# esp8266_01.net
KiCad netlist of a schematic drawn in EAGLE
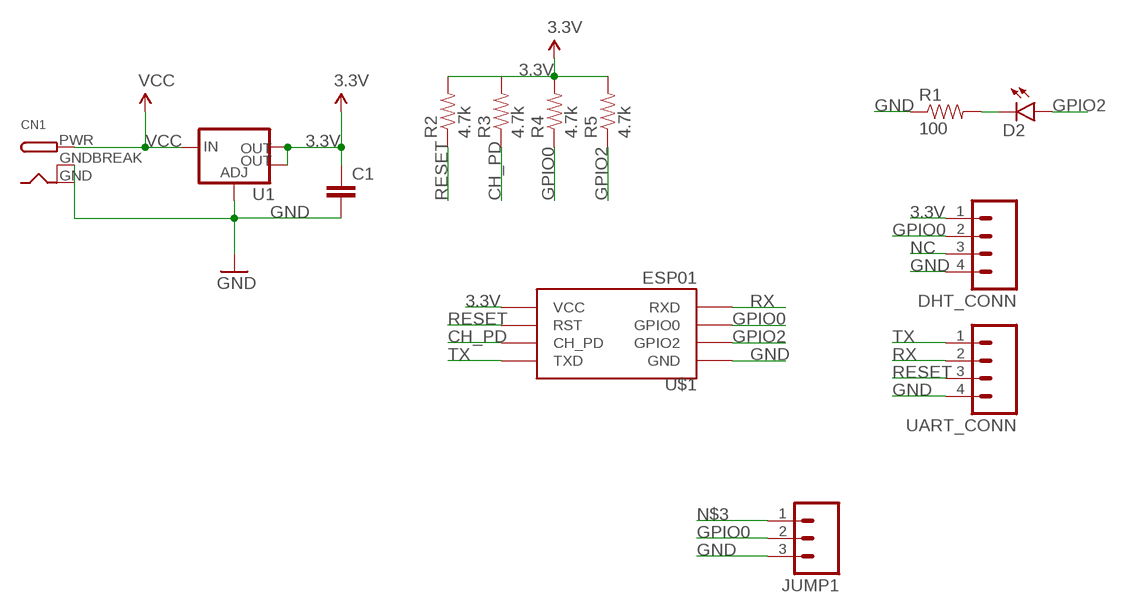
[diagram p0: schematic, sheet 1]

(export (version "E")
  (design (tool "Eeschema 10.0.6"))
  (components
    (comp (ref "C1")
      (value "CAP0805")
      (footprint "eagle-import:0805")
      (libsource (lib "eagle-import") (part "CAP0805"))
    )
    (comp (ref "CN1")
      (value "DCBARRELPTH")
      (footprint "eagle-import:DCJACK_2MM_PTH")
      (libsource (lib "eagle-import") (part "DCBARRELPTH"))
    )
    (comp (ref "D2")
      (value "LED5MM")
      (footprint "eagle-import:LED5MM")
      (libsource (lib "eagle-import") (part "LED5MM"))
    )
    (comp (ref "DHT_CONN")
      (value "M04LONGPADS")
      (footprint "eagle-import:1X04_LONGPADS")
      (libsource (lib "eagle-import") (part "M04LONGPADS"))
    )
    (comp (ref "JUMP1")
      (value "M03LOCK_LONGPADS")
      (footprint "eagle-import:1X03_LOCK_LONGPADS")
      (libsource (lib "eagle-import") (part "M03LOCK_LONGPADS"))
    )
    (comp (ref "R1")
      (value "100")
      (footprint "eagle-import:0805")
      (libsource (lib "eagle-import") (part "RESISTOR0805-RES"))
    )
    (comp (ref "R2")
      (value "4.7k")
      (footprint "eagle-import:0805")
      (libsource (lib "eagle-import") (part "RESISTOR0805-RES"))
    )
    (comp (ref "R3")
      (value "4.7k")
      (footprint "eagle-import:0805")
      (libsource (lib "eagle-import") (part "RESISTOR0805-RES"))
    )
    (comp (ref "R4")
      (value "4.7k")
      (footprint "eagle-import:0805")
      (libsource (lib "eagle-import") (part "RESISTOR0805-RES"))
    )
    (comp (ref "R5")
      (value "4.7k")
      (footprint "eagle-import:0805")
      (libsource (lib "eagle-import") (part "RESISTOR0805-RES"))
    )
    (comp (ref "U$1")
      (value "ESP01")
      (footprint "eagle-import:ESP01")
      (libsource (lib "eagle-import") (part "ESP01"))
    )
    (comp (ref "U1")
      (value "V_REG_LM1117SOT223")
      (footprint "eagle-import:SOT223")
      (libsource (lib "eagle-import") (part "V_REG_LM1117SOT223"))
    )
    (comp (ref "UART_CONN")
      (value "M04LONGPADS")
      (footprint "eagle-import:1X04_LONGPADS")
      (libsource (lib "eagle-import") (part "M04LONGPADS"))
    )
  )
  (nets
    (net (code "1") (name "/CH_PD") (class "Default")
      (node (ref "R3") (pin "1") (pinfunction "1_1") (pintype "passive"))
      (node (ref "U$1") (pin "CH_PD") (pinfunction "CH_PD_CH_PD") (pintype "bidirectional"))
    )
    (net (code "2") (name "/GPIO0") (class "Default")
      (node (ref "DHT_CONN") (pin "2") (pinfunction "2_2") (pintype "passive"))
      (node (ref "JUMP1") (pin "2") (pinfunction "2_2") (pintype "passive"))
      (node (ref "R4") (pin "1") (pinfunction "1_1") (pintype "passive"))
      (node (ref "U$1") (pin "GPIO0") (pinfunction "GPIO0_GPIO0") (pintype "bidirectional"))
    )
    (net (code "3") (name "/GPIO2") (class "Default")
      (node (ref "D2") (pin "A") (pinfunction "A_A") (pintype "passive"))
      (node (ref "R5") (pin "1") (pinfunction "1_1") (pintype "passive"))
      (node (ref "U$1") (pin "GPIO2") (pinfunction "GPIO2_GPIO2") (pintype "bidirectional"))
    )
    (net (code "4") (name "/N$3") (class "Default")
      (node (ref "JUMP1") (pin "1") (pinfunction "1_1") (pintype "passive"))
    )
    (net (code "5") (name "/NC") (class "Default")
      (node (ref "DHT_CONN") (pin "3") (pinfunction "3_3") (pintype "passive"))
    )
    (net (code "6") (name "/RESET") (class "Default")
      (node (ref "R2") (pin "1") (pinfunction "1_1") (pintype "passive"))
      (node (ref "U$1") (pin "RST") (pinfunction "RST_RST") (pintype "bidirectional"))
      (node (ref "UART_CONN") (pin "3") (pinfunction "3_3") (pintype "passive"))
    )
    (net (code "7") (name "/RX") (class "Default")
      (node (ref "U$1") (pin "RX") (pinfunction "RXD_RX") (pintype "bidirectional"))
      (node (ref "UART_CONN") (pin "2") (pinfunction "2_2") (pintype "passive"))
    )
    (net (code "8") (name "/TX") (class "Default")
      (node (ref "U$1") (pin "TX") (pinfunction "TXD_TX") (pintype "bidirectional"))
      (node (ref "UART_CONN") (pin "1") (pinfunction "1_1") (pintype "passive"))
    )
    (net (code "9") (name "3.3V") (class "Default")
      (node (ref "C1") (pin "1") (pinfunction "1_1") (pintype "passive"))
      (node (ref "DHT_CONN") (pin "1") (pinfunction "1_1") (pintype "passive"))
      (node (ref "R2") (pin "2") (pinfunction "2_2") (pintype "passive"))
      (node (ref "R3") (pin "2") (pinfunction "2_2") (pintype "passive"))
      (node (ref "R4") (pin "2") (pinfunction "2_2") (pintype "passive"))
      (node (ref "R5") (pin "2") (pinfunction "2_2") (pintype "passive"))
      (node (ref "U$1") (pin "VCC") (pinfunction "VCC_VCC") (pintype "bidirectional"))
      (node (ref "U1") (pin "2") (pinfunction "OUT_2") (pintype "output"))
      (node (ref "U1") (pin "4") (pinfunction "OUT_4") (pintype "output"))
    )
    (net (code "10") (name "GND") (class "Default")
      (node (ref "C1") (pin "2") (pinfunction "2_2") (pintype "passive"))
      (node (ref "CN1") (pin "GND") (pinfunction "GND_GND") (pintype "power_in"))
      (node (ref "CN1") (pin "GNDBREAK") (pinfunction "GNDBREAK_GNDBREAK") (pintype "power_in"))
      (node (ref "DHT_CONN") (pin "4") (pinfunction "4_4") (pintype "passive"))
      (node (ref "JUMP1") (pin "3") (pinfunction "3_3") (pintype "passive"))
      (node (ref "R1") (pin "1") (pinfunction "1_1") (pintype "passive"))
      (node (ref "U$1") (pin "GND") (pinfunction "GND_GND") (pintype "bidirectional"))
      (node (ref "U1") (pin "1") (pinfunction "ADJ_1") (pintype "input"))
      (node (ref "UART_CONN") (pin "4") (pinfunction "4_4") (pintype "passive"))
    )
    (net (code "11") (name "Net-(D2-C)") (class "Default")
      (node (ref "D2") (pin "K") (pinfunction "C_K") (pintype "passive"))
      (node (ref "R1") (pin "2") (pinfunction "2_2") (pintype "passive"))
    )
    (net (code "12") (name "VCC") (class "Default")
      (node (ref "CN1") (pin "PWR") (pinfunction "PWR_PWR") (pintype "power_in"))
      (node (ref "U1") (pin "3") (pinfunction "IN_3") (pintype "input"))
    )
  )
)
